# offsets-7x.net
KiCad netlist of a schematic drawn in EAGLE
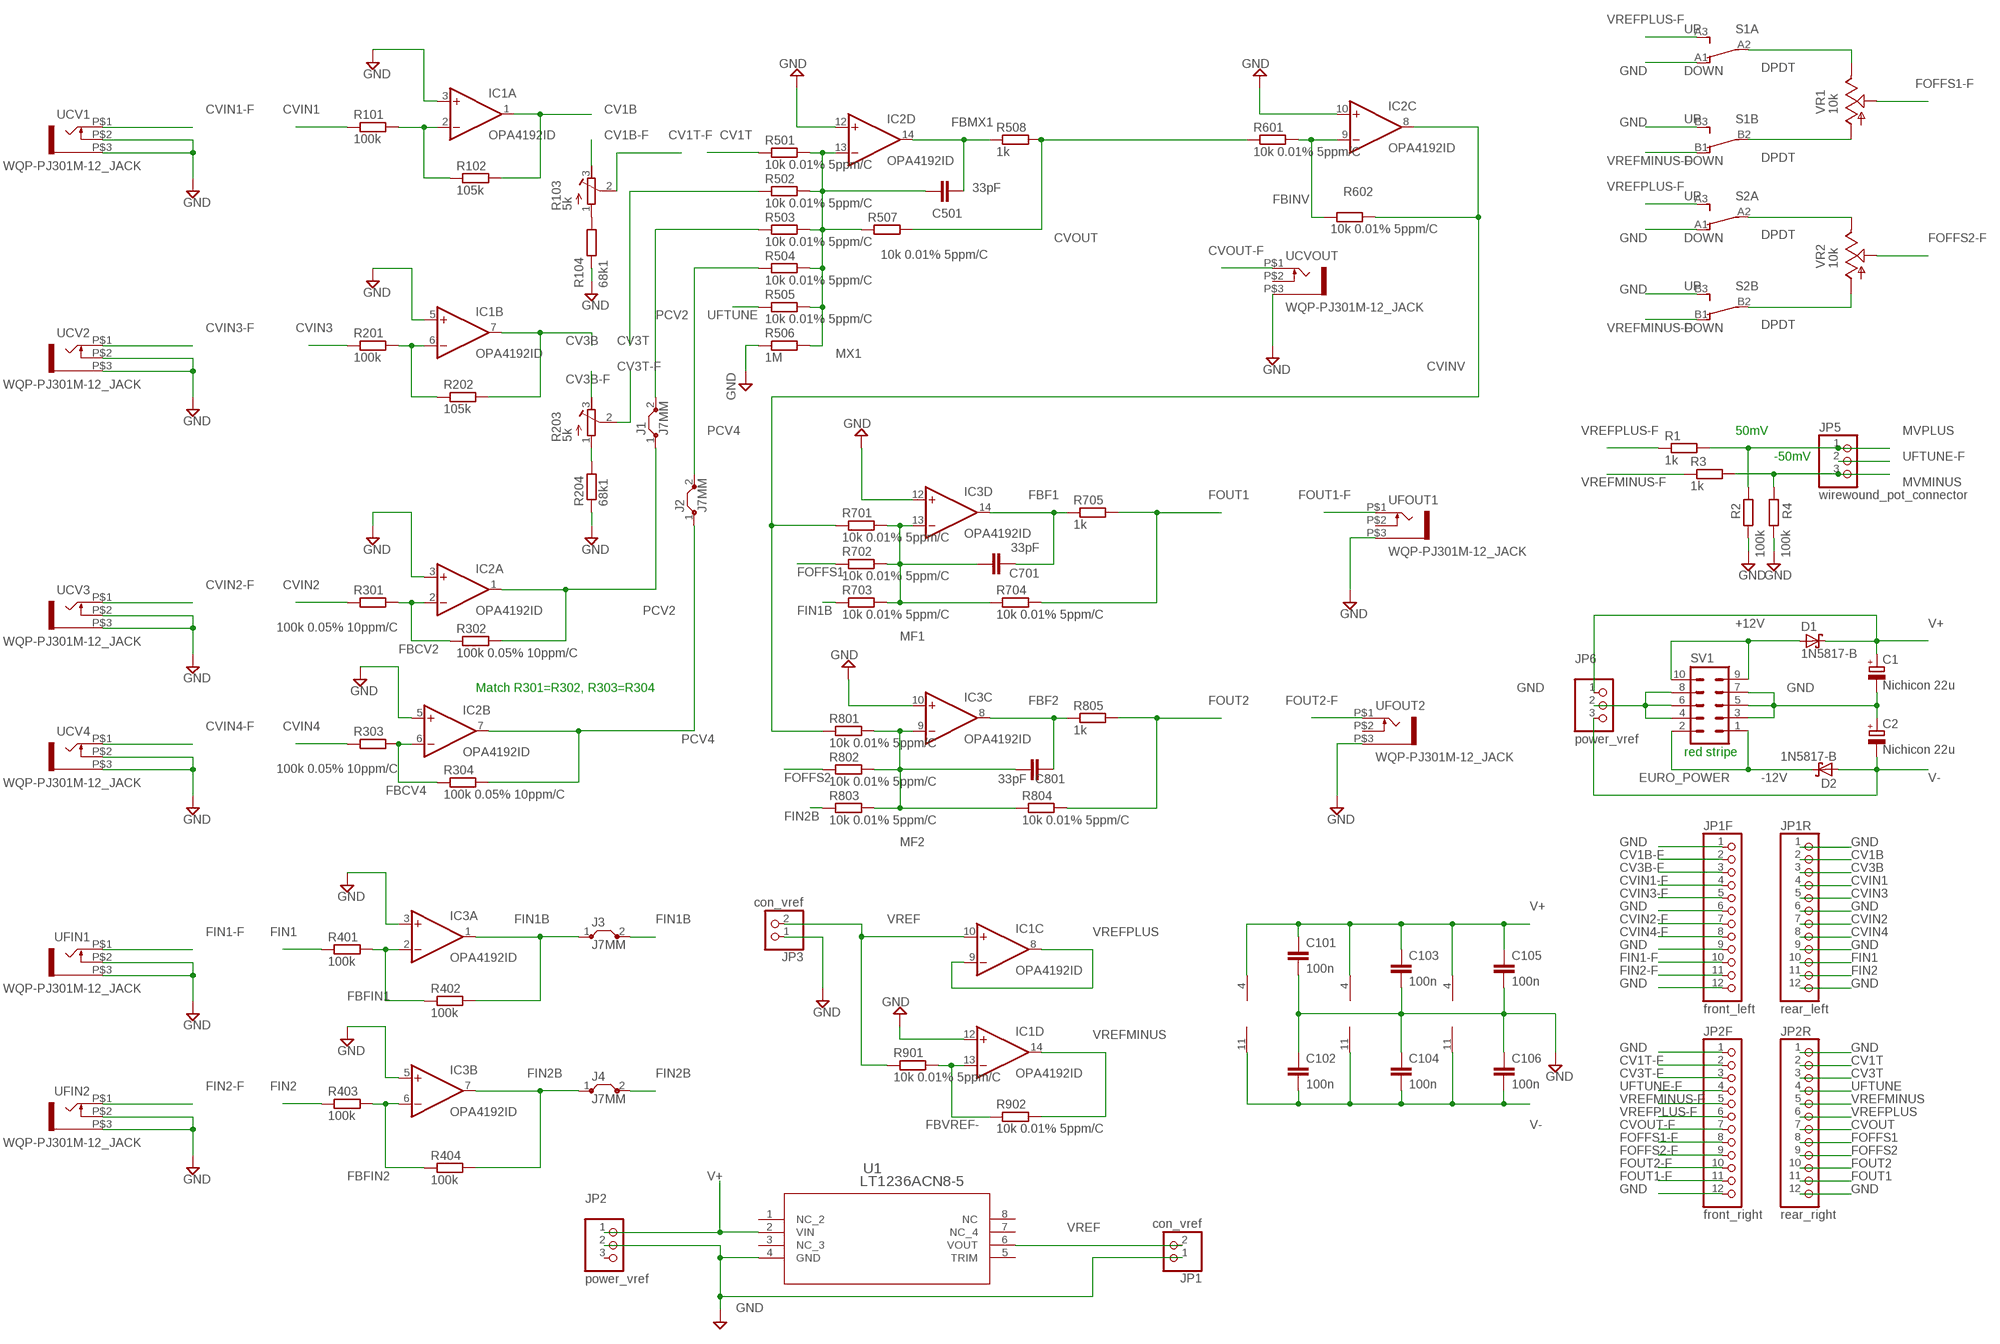
[diagram p0: schematic, sheet 1]

(export (version "E")
  (design (tool "Eeschema 10.0.6"))
  (components
    (comp (ref "C1")
      (value "Nichicon 22u")
      (footprint "eagle-import:E2,5-5")
      (libsource (lib "eagle-import") (part "CPOL-EUE2.5-5"))
    )
    (comp (ref "C2")
      (value "Nichicon 22u")
      (footprint "eagle-import:E2,5-5")
      (libsource (lib "eagle-import") (part "CPOL-EUE2.5-5"))
    )
    (comp (ref "C101")
      (value "100n")
      (footprint "eagle-import:C1206")
      (libsource (lib "eagle-import") (part "C-EUC1206"))
    )
    (comp (ref "C102")
      (value "100n")
      (footprint "eagle-import:C1206")
      (libsource (lib "eagle-import") (part "C-EUC1206"))
    )
    (comp (ref "C103")
      (value "100n")
      (footprint "eagle-import:C1206")
      (libsource (lib "eagle-import") (part "C-EUC1206"))
    )
    (comp (ref "C104")
      (value "100n")
      (footprint "eagle-import:C1206")
      (libsource (lib "eagle-import") (part "C-EUC1206"))
    )
    (comp (ref "C105")
      (value "100n")
      (footprint "eagle-import:C1206")
      (libsource (lib "eagle-import") (part "C-EUC1206"))
    )
    (comp (ref "C106")
      (value "100n")
      (footprint "eagle-import:C1206")
      (libsource (lib "eagle-import") (part "C-EUC1206"))
    )
    (comp (ref "C501")
      (value "33pF")
      (footprint "eagle-import:C0805K")
      (libsource (lib "eagle-import") (part "C-EUC0805K"))
    )
    (comp (ref "C701")
      (value "33pF")
      (footprint "eagle-import:C0805K")
      (libsource (lib "eagle-import") (part "C-EUC0805K"))
    )
    (comp (ref "C801")
      (value "33pF")
      (footprint "eagle-import:C0805K")
      (libsource (lib "eagle-import") (part "C-EUC0805K"))
    )
    (comp (ref "D1")
      (value "1N5817-B")
      (footprint "eagle-import:DO41-7.6")
      (libsource (lib "eagle-import") (part "1N5817-B"))
    )
    (comp (ref "D2")
      (value "1N5817-B")
      (footprint "eagle-import:DO41-7.6")
      (libsource (lib "eagle-import") (part "1N5817-B"))
    )
    (comp (ref "IC1")
      (value "OPA4192ID")
      (footprint "eagle-import:SO14")
      (libsource (lib "eagle-import") (part "TL074D"))
    )
    (comp (ref "IC2")
      (value "OPA4192ID")
      (footprint "eagle-import:SO14")
      (libsource (lib "eagle-import") (part "TL074D"))
    )
    (comp (ref "IC3")
      (value "OPA4192ID")
      (footprint "eagle-import:SO14")
      (libsource (lib "eagle-import") (part "TL074D"))
    )
    (comp (ref "J1")
      (value "J7MM")
      (footprint "eagle-import:07")
      (libsource (lib "eagle-import") (part "J7MM"))
    )
    (comp (ref "J2")
      (value "J7MM")
      (footprint "eagle-import:07")
      (libsource (lib "eagle-import") (part "J7MM"))
    )
    (comp (ref "J3")
      (value "J7MM")
      (footprint "eagle-import:07")
      (libsource (lib "eagle-import") (part "J7MM"))
    )
    (comp (ref "J4")
      (value "J7MM")
      (footprint "eagle-import:07")
      (libsource (lib "eagle-import") (part "J7MM"))
    )
    (comp (ref "JP1")
      (value "con_vref")
      (footprint "eagle-import:1X02")
      (libsource (lib "eagle-import") (part "PINHD-1X2"))
    )
    (comp (ref "JP1F")
      (value "front_left")
      (footprint "eagle-import:1X12")
      (libsource (lib "eagle-import") (part "PINHD-1X12"))
    )
    (comp (ref "JP1R")
      (value "rear_left")
      (footprint "eagle-import:1X12")
      (libsource (lib "eagle-import") (part "PINHD-1X12"))
    )
    (comp (ref "JP2")
      (value "power_vref")
      (footprint "eagle-import:1X03")
      (libsource (lib "eagle-import") (part "PINHD-1X3"))
    )
    (comp (ref "JP2F")
      (value "front_right")
      (footprint "eagle-import:1X12")
      (libsource (lib "eagle-import") (part "PINHD-1X12"))
    )
    (comp (ref "JP2R")
      (value "rear_right")
      (footprint "eagle-import:1X12")
      (libsource (lib "eagle-import") (part "PINHD-1X12"))
    )
    (comp (ref "JP3")
      (value "con_vref")
      (footprint "eagle-import:1X02")
      (libsource (lib "eagle-import") (part "PINHD-1X2"))
    )
    (comp (ref "JP5")
      (value "wirewound_pot_connector")
      (footprint "eagle-import:1X03")
      (libsource (lib "eagle-import") (part "PINHD-1X3"))
    )
    (comp (ref "JP6")
      (value "power_vref")
      (footprint "eagle-import:1X03")
      (libsource (lib "eagle-import") (part "PINHD-1X3"))
    )
    (comp (ref "R1")
      (value "1k")
      (footprint "eagle-import:R0805W")
      (libsource (lib "eagle-import") (part "R-EU_R0805W"))
    )
    (comp (ref "R2")
      (value "100k")
      (footprint "eagle-import:R0805W")
      (libsource (lib "eagle-import") (part "R-EU_R0805W"))
    )
    (comp (ref "R3")
      (value "1k")
      (footprint "eagle-import:R0805W")
      (libsource (lib "eagle-import") (part "R-EU_R0805W"))
    )
    (comp (ref "R4")
      (value "100k")
      (footprint "eagle-import:R0805W")
      (libsource (lib "eagle-import") (part "R-EU_R0805W"))
    )
    (comp (ref "R101")
      (value "100k")
      (footprint "eagle-import:R0805W")
      (libsource (lib "eagle-import") (part "R-EU_R0805W"))
    )
    (comp (ref "R102")
      (value "105k")
      (footprint "eagle-import:R0805W")
      (libsource (lib "eagle-import") (part "R-EU_R0805W"))
    )
    (comp (ref "R103")
      (value "5k")
      (footprint "eagle-import:RTRIM3296W")
      (libsource (lib "eagle-import") (part "R-TRIMM3296W"))
    )
    (comp (ref "R104")
      (value "68k1")
      (footprint "eagle-import:R0805W")
      (libsource (lib "eagle-import") (part "R-EU_R0805W"))
    )
    (comp (ref "R201")
      (value "100k")
      (footprint "eagle-import:R0805W")
      (libsource (lib "eagle-import") (part "R-EU_R0805W"))
    )
    (comp (ref "R202")
      (value "105k")
      (footprint "eagle-import:R0805W")
      (libsource (lib "eagle-import") (part "R-EU_R0805W"))
    )
    (comp (ref "R203")
      (value "5k")
      (footprint "eagle-import:RTRIM3296W")
      (libsource (lib "eagle-import") (part "R-TRIMM3296W"))
    )
    (comp (ref "R204")
      (value "68k1")
      (footprint "eagle-import:R0805W")
      (libsource (lib "eagle-import") (part "R-EU_R0805W"))
    )
    (comp (ref "R301")
      (value "100k 0.05% 10ppm/C")
      (footprint "eagle-import:R0805W")
      (libsource (lib "eagle-import") (part "R-EU_R0805W"))
    )
    (comp (ref "R302")
      (value "100k 0.05% 10ppm/C")
      (footprint "eagle-import:R0805W")
      (libsource (lib "eagle-import") (part "R-EU_R0805W"))
    )
    (comp (ref "R303")
      (value "100k 0.05% 10ppm/C")
      (footprint "eagle-import:R0805W")
      (libsource (lib "eagle-import") (part "R-EU_R0805W"))
    )
    (comp (ref "R304")
      (value "100k 0.05% 10ppm/C")
      (footprint "eagle-import:R0805W")
      (libsource (lib "eagle-import") (part "R-EU_R0805W"))
    )
    (comp (ref "R401")
      (value "100k")
      (footprint "eagle-import:R0805W")
      (libsource (lib "eagle-import") (part "R-EU_R0805W"))
    )
    (comp (ref "R402")
      (value "100k")
      (footprint "eagle-import:R0805W")
      (libsource (lib "eagle-import") (part "R-EU_R0805W"))
    )
    (comp (ref "R403")
      (value "100k")
      (footprint "eagle-import:R0805W")
      (libsource (lib "eagle-import") (part "R-EU_R0805W"))
    )
    (comp (ref "R404")
      (value "100k")
      (footprint "eagle-import:R0805W")
      (libsource (lib "eagle-import") (part "R-EU_R0805W"))
    )
    (comp (ref "R501")
      (value "10k 0.01% 5ppm/C")
      (footprint "eagle-import:R0805W")
      (libsource (lib "eagle-import") (part "R-EU_R0805W"))
    )
    (comp (ref "R502")
      (value "10k 0.01% 5ppm/C")
      (footprint "eagle-import:R0805W")
      (libsource (lib "eagle-import") (part "R-EU_R0805W"))
    )
    (comp (ref "R503")
      (value "10k 0.01% 5ppm/C")
      (footprint "eagle-import:R0805W")
      (libsource (lib "eagle-import") (part "R-EU_R0805W"))
    )
    (comp (ref "R504")
      (value "10k 0.01% 5ppm/C")
      (footprint "eagle-import:R0805W")
      (libsource (lib "eagle-import") (part "R-EU_R0805W"))
    )
    (comp (ref "R505")
      (value "10k 0.01% 5ppm/C")
      (footprint "eagle-import:R0805W")
      (libsource (lib "eagle-import") (part "R-EU_R0805W"))
    )
    (comp (ref "R506")
      (value "1M")
      (footprint "eagle-import:R0805W")
      (libsource (lib "eagle-import") (part "R-EU_R0805W"))
    )
    (comp (ref "R507")
      (value "10k 0.01% 5ppm/C")
      (footprint "eagle-import:R0805W")
      (libsource (lib "eagle-import") (part "R-EU_R0805W"))
    )
    (comp (ref "R508")
      (value "1k")
      (footprint "eagle-import:R0805W")
      (libsource (lib "eagle-import") (part "R-EU_R0805W"))
    )
    (comp (ref "R601")
      (value "10k 0.01% 5ppm/C")
      (footprint "eagle-import:R0805W")
      (libsource (lib "eagle-import") (part "R-EU_R0805W"))
    )
    (comp (ref "R602")
      (value "10k 0.01% 5ppm/C")
      (footprint "eagle-import:R0805W")
      (libsource (lib "eagle-import") (part "R-EU_R0805W"))
    )
    (comp (ref "R701")
      (value "10k 0.01% 5ppm/C")
      (footprint "eagle-import:R0805W")
      (libsource (lib "eagle-import") (part "R-EU_R0805W"))
    )
    (comp (ref "R702")
      (value "10k 0.01% 5ppm/C")
      (footprint "eagle-import:R0805W")
      (libsource (lib "eagle-import") (part "R-EU_R0805W"))
    )
    (comp (ref "R703")
      (value "10k 0.01% 5ppm/C")
      (footprint "eagle-import:R0805W")
      (libsource (lib "eagle-import") (part "R-EU_R0805W"))
    )
    (comp (ref "R704")
      (value "10k 0.01% 5ppm/C")
      (footprint "eagle-import:R0805W")
      (libsource (lib "eagle-import") (part "R-EU_R0805W"))
    )
    (comp (ref "R705")
      (value "1k")
      (footprint "eagle-import:R0805W")
      (libsource (lib "eagle-import") (part "R-EU_R0805W"))
    )
    (comp (ref "R801")
      (value "10k 0.01% 5ppm/C")
      (footprint "eagle-import:R0805W")
      (libsource (lib "eagle-import") (part "R-EU_R0805W"))
    )
    (comp (ref "R802")
      (value "10k 0.01% 5ppm/C")
      (footprint "eagle-import:R0805W")
      (libsource (lib "eagle-import") (part "R-EU_R0805W"))
    )
    (comp (ref "R803")
      (value "10k 0.01% 5ppm/C")
      (footprint "eagle-import:R0805W")
      (libsource (lib "eagle-import") (part "R-EU_R0805W"))
    )
    (comp (ref "R804")
      (value "10k 0.01% 5ppm/C")
      (footprint "eagle-import:R0805W")
      (libsource (lib "eagle-import") (part "R-EU_R0805W"))
    )
    (comp (ref "R805")
      (value "1k")
      (footprint "eagle-import:R0805W")
      (libsource (lib "eagle-import") (part "R-EU_R0805W"))
    )
    (comp (ref "R901")
      (value "10k 0.01% 5ppm/C")
      (footprint "eagle-import:R0805W")
      (libsource (lib "eagle-import") (part "R-EU_R0805W"))
    )
    (comp (ref "R902")
      (value "10k 0.01% 5ppm/C")
      (footprint "eagle-import:R0805W")
      (libsource (lib "eagle-import") (part "R-EU_R0805W"))
    )
    (comp (ref "S1")
      (value "DPDT")
      (footprint "eagle-import:DPDT-VERTICAL-TOP-SUBMINI-MULTICOMP")
      (libsource (lib "eagle-import") (part "DPDT-VERTICAL-DOWNTOP-SUBMINI"))
    )
    (comp (ref "S2")
      (value "DPDT")
      (footprint "eagle-import:DPDT-VERTICAL-TOP-SUBMINI-MULTICOMP")
      (libsource (lib "eagle-import") (part "DPDT-VERTICAL-DOWNTOP-SUBMINI"))
    )
    (comp (ref "SV1")
      (value "EURO_POWER")
      (footprint "eagle-import:EURO_POWER_HEADER")
      (libsource (lib "eagle-import") (part "EURO_POWER_HEADERREGULAR"))
    )
    (comp (ref "U1")
      (value "LT1236ACN8-5")
      (footprint "eagle-import:PDIP-8_N")
      (fields (field (name "MANUFACTURER_PART_NUMBER") "lt1236acn810"))
      (libsource (lib "eagle-import") (part "LT1236ACN8-10"))
    )
    (comp (ref "UCV1")
      (value "WQP-PJ301M-12_JACK")
      (footprint "eagle-import:WQP-PJ301M-12_JACK")
      (libsource (lib "eagle-import") (part "WQP-PJ301M-12_JACK"))
    )
    (comp (ref "UCV2")
      (value "WQP-PJ301M-12_JACK")
      (footprint "eagle-import:WQP-PJ301M-12_JACK")
      (libsource (lib "eagle-import") (part "WQP-PJ301M-12_JACK"))
    )
    (comp (ref "UCV3")
      (value "WQP-PJ301M-12_JACK")
      (footprint "eagle-import:WQP-PJ301M-12_JACK")
      (libsource (lib "eagle-import") (part "WQP-PJ301M-12_JACK"))
    )
    (comp (ref "UCV4")
      (value "WQP-PJ301M-12_JACK")
      (footprint "eagle-import:WQP-PJ301M-12_JACK")
      (libsource (lib "eagle-import") (part "WQP-PJ301M-12_JACK"))
    )
    (comp (ref "UCVOUT")
      (value "WQP-PJ301M-12_JACK")
      (footprint "eagle-import:WQP-PJ301M-12_JACK")
      (libsource (lib "eagle-import") (part "WQP-PJ301M-12_JACK"))
    )
    (comp (ref "UFIN1")
      (value "WQP-PJ301M-12_JACK")
      (footprint "eagle-import:WQP-PJ301M-12_JACK")
      (libsource (lib "eagle-import") (part "WQP-PJ301M-12_JACK"))
    )
    (comp (ref "UFIN2")
      (value "WQP-PJ301M-12_JACK")
      (footprint "eagle-import:WQP-PJ301M-12_JACK")
      (libsource (lib "eagle-import") (part "WQP-PJ301M-12_JACK"))
    )
    (comp (ref "UFOUT1")
      (value "WQP-PJ301M-12_JACK")
      (footprint "eagle-import:WQP-PJ301M-12_JACK")
      (libsource (lib "eagle-import") (part "WQP-PJ301M-12_JACK"))
    )
    (comp (ref "UFOUT2")
      (value "WQP-PJ301M-12_JACK")
      (footprint "eagle-import:WQP-PJ301M-12_JACK")
      (libsource (lib "eagle-import") (part "WQP-PJ301M-12_JACK"))
    )
    (comp (ref "VR1")
      (value "10k")
      (footprint "eagle-import:9MM_SNAP-IN_POT")
      (libsource (lib "eagle-import") (part "9MM_SNAP-IN_POT_"))
    )
    (comp (ref "VR2")
      (value "10k")
      (footprint "eagle-import:9MM_SNAP-IN_POT")
      (libsource (lib "eagle-import") (part "9MM_SNAP-IN_POT_"))
    )
  )
  (nets
    (net (code "1") (name "/+12V") (class "Default")
      (node (ref "D1") (pin "A") (pinfunction "A_A") (pintype "passive"))
      (node (ref "SV1") (pin "10") (pinfunction "10_10") (pintype "passive"))
      (node (ref "SV1") (pin "9") (pinfunction "9_9") (pintype "passive"))
    )
    (net (code "2") (name "/-12V") (class "Default")
      (node (ref "D2") (pin "C") (pinfunction "C_C") (pintype "passive"))
      (node (ref "SV1") (pin "1") (pinfunction "1_1") (pintype "passive"))
      (node (ref "SV1") (pin "2") (pinfunction "2_2") (pintype "passive"))
    )
    (net (code "3") (name "/CV1B") (class "Default")
      (node (ref "IC1") (pin "1") (pinfunction "OUT_1") (pintype "output"))
      (node (ref "JP1R") (pin "2") (pinfunction "2_2") (pintype "passive"))
      (node (ref "R102") (pin "2") (pinfunction "2_2") (pintype "passive"))
    )
    (net (code "4") (name "/CV1B-F") (class "Default")
      (node (ref "JP1F") (pin "2") (pinfunction "2_2") (pintype "passive"))
      (node (ref "R103") (pin "3") (pinfunction "E_3") (pintype "passive"))
    )
    (net (code "5") (name "/CV1T") (class "Default")
      (node (ref "JP2R") (pin "2") (pinfunction "2_2") (pintype "passive"))
      (node (ref "R501") (pin "1") (pinfunction "1_1") (pintype "passive"))
    )
    (net (code "6") (name "/CV1T-F") (class "Default")
      (node (ref "JP2F") (pin "2") (pinfunction "2_2") (pintype "passive"))
      (node (ref "R103") (pin "2") (pinfunction "S_2") (pintype "passive"))
    )
    (net (code "7") (name "/CV3B") (class "Default")
      (node (ref "IC1") (pin "7") (pinfunction "OUT_7") (pintype "output"))
      (node (ref "JP1R") (pin "3") (pinfunction "3_3") (pintype "passive"))
      (node (ref "R202") (pin "2") (pinfunction "2_2") (pintype "passive"))
    )
    (net (code "8") (name "/CV3B-F") (class "Default")
      (node (ref "JP1F") (pin "3") (pinfunction "3_3") (pintype "passive"))
      (node (ref "R203") (pin "3") (pinfunction "E_3") (pintype "passive"))
    )
    (net (code "9") (name "/CV3T") (class "Default")
      (node (ref "JP2R") (pin "3") (pinfunction "3_3") (pintype "passive"))
      (node (ref "R502") (pin "1") (pinfunction "1_1") (pintype "passive"))
    )
    (net (code "10") (name "/CV3T-F") (class "Default")
      (node (ref "JP2F") (pin "3") (pinfunction "3_3") (pintype "passive"))
      (node (ref "R203") (pin "2") (pinfunction "S_2") (pintype "passive"))
    )
    (net (code "11") (name "/CVIN1") (class "Default")
      (node (ref "JP1R") (pin "4") (pinfunction "4_4") (pintype "passive"))
      (node (ref "R101") (pin "1") (pinfunction "1_1") (pintype "passive"))
    )
    (net (code "12") (name "/CVIN1-F") (class "Default")
      (node (ref "JP1F") (pin "4") (pinfunction "4_4") (pintype "passive"))
      (node (ref "UCV1") (pin "P$1") (pinfunction "2_P$1") (pintype "passive"))
    )
    (net (code "13") (name "/CVIN2") (class "Default")
      (node (ref "JP1R") (pin "7") (pinfunction "7_7") (pintype "passive"))
      (node (ref "R301") (pin "1") (pinfunction "1_1") (pintype "passive"))
    )
    (net (code "14") (name "/CVIN2-F") (class "Default")
      (node (ref "JP1F") (pin "7") (pinfunction "7_7") (pintype "passive"))
      (node (ref "UCV3") (pin "P$1") (pinfunction "2_P$1") (pintype "passive"))
    )
    (net (code "15") (name "/CVIN3") (class "Default")
      (node (ref "JP1R") (pin "5") (pinfunction "5_5") (pintype "passive"))
      (node (ref "R201") (pin "1") (pinfunction "1_1") (pintype "passive"))
    )
    (net (code "16") (name "/CVIN3-F") (class "Default")
      (node (ref "JP1F") (pin "5") (pinfunction "5_5") (pintype "passive"))
      (node (ref "UCV2") (pin "P$1") (pinfunction "2_P$1") (pintype "passive"))
    )
    (net (code "17") (name "/CVIN4") (class "Default")
      (node (ref "JP1R") (pin "8") (pinfunction "8_8") (pintype "passive"))
      (node (ref "R303") (pin "1") (pinfunction "1_1") (pintype "passive"))
    )
    (net (code "18") (name "/CVIN4-F") (class "Default")
      (node (ref "JP1F") (pin "8") (pinfunction "8_8") (pintype "passive"))
      (node (ref "UCV4") (pin "P$1") (pinfunction "2_P$1") (pintype "passive"))
    )
    (net (code "19") (name "/CVINV") (class "Default")
      (node (ref "IC2") (pin "8") (pinfunction "OUT_8") (pintype "output"))
      (node (ref "R602") (pin "2") (pinfunction "2_2") (pintype "passive"))
      (node (ref "R701") (pin "1") (pinfunction "1_1") (pintype "passive"))
      (node (ref "R801") (pin "1") (pinfunction "1_1") (pintype "passive"))
    )
    (net (code "20") (name "/CVOUT") (class "Default")
      (node (ref "JP2R") (pin "7") (pinfunction "7_7") (pintype "passive"))
      (node (ref "R507") (pin "2") (pinfunction "2_2") (pintype "passive"))
      (node (ref "R508") (pin "2") (pinfunction "2_2") (pintype "passive"))
      (node (ref "R601") (pin "1") (pinfunction "1_1") (pintype "passive"))
    )
    (net (code "21") (name "/CVOUT-F") (class "Default")
      (node (ref "JP2F") (pin "7") (pinfunction "7_7") (pintype "passive"))
      (node (ref "UCVOUT") (pin "P$1") (pinfunction "2_P$1") (pintype "passive"))
    )
    (net (code "22") (name "/FBCV2") (class "Default")
      (node (ref "IC2") (pin "2") (pinfunction "-IN_2") (pintype "input"))
      (node (ref "R301") (pin "2") (pinfunction "2_2") (pintype "passive"))
      (node (ref "R302") (pin "1") (pinfunction "1_1") (pintype "passive"))
    )
    (net (code "23") (name "/FBCV4") (class "Default")
      (node (ref "IC2") (pin "6") (pinfunction "-IN_6") (pintype "input"))
      (node (ref "R303") (pin "2") (pinfunction "2_2") (pintype "passive"))
      (node (ref "R304") (pin "1") (pinfunction "1_1") (pintype "passive"))
    )
    (net (code "24") (name "/FBF1") (class "Default")
      (node (ref "C701") (pin "2") (pinfunction "2_2") (pintype "passive"))
      (node (ref "IC3") (pin "14") (pinfunction "OUT_14") (pintype "output"))
      (node (ref "R705") (pin "1") (pinfunction "1_1") (pintype "passive"))
    )
    (net (code "25") (name "/FBF2") (class "Default")
      (node (ref "C801") (pin "2") (pinfunction "2_2") (pintype "passive"))
      (node (ref "IC3") (pin "8") (pinfunction "OUT_8") (pintype "output"))
      (node (ref "R805") (pin "1") (pinfunction "1_1") (pintype "passive"))
    )
    (net (code "26") (name "/FBFIN1") (class "Default")
      (node (ref "IC3") (pin "2") (pinfunction "-IN_2") (pintype "input"))
      (node (ref "R401") (pin "2") (pinfunction "2_2") (pintype "passive"))
      (node (ref "R402") (pin "1") (pinfunction "1_1") (pintype "passive"))
    )
    (net (code "27") (name "/FBFIN2") (class "Default")
      (node (ref "IC3") (pin "6") (pinfunction "-IN_6") (pintype "input"))
      (node (ref "R403") (pin "2") (pinfunction "2_2") (pintype "passive"))
      (node (ref "R404") (pin "1") (pinfunction "1_1") (pintype "passive"))
    )
    (net (code "28") (name "/FBINV") (class "Default")
      (node (ref "IC2") (pin "9") (pinfunction "-IN_9") (pintype "input"))
      (node (ref "R601") (pin "2") (pinfunction "2_2") (pintype "passive"))
      (node (ref "R602") (pin "1") (pinfunction "1_1") (pintype "passive"))
    )
    (net (code "29") (name "/FBMX1") (class "Default")
      (node (ref "C501") (pin "2") (pinfunction "2_2") (pintype "passive"))
      (node (ref "IC2") (pin "14") (pinfunction "OUT_14") (pintype "output"))
      (node (ref "R508") (pin "1") (pinfunction "1_1") (pintype "passive"))
    )
    (net (code "30") (name "/FBVREF-") (class "Default")
      (node (ref "IC1") (pin "13") (pinfunction "-IN_13") (pintype "input"))
      (node (ref "R901") (pin "2") (pinfunction "2_2") (pintype "passive"))
      (node (ref "R902") (pin "1") (pinfunction "1_1") (pintype "passive"))
    )
    (net (code "31") (name "/FIN1") (class "Default")
      (node (ref "JP1R") (pin "10") (pinfunction "10_10") (pintype "passive"))
      (node (ref "R401") (pin "1") (pinfunction "1_1") (pintype "passive"))
    )
    (net (code "32") (name "/FIN1-F") (class "Default")
      (node (ref "JP1F") (pin "10") (pinfunction "10_10") (pintype "passive"))
      (node (ref "UFIN1") (pin "P$1") (pinfunction "2_P$1") (pintype "passive"))
    )
    (net (code "33") (name "/FIN1B") (class "Default")
      (node (ref "IC3") (pin "1") (pinfunction "OUT_1") (pintype "output"))
      (node (ref "J3") (pin "1") (pinfunction "1_1") (pintype "passive"))
      (node (ref "J3") (pin "2") (pinfunction "2_2") (pintype "passive"))
      (node (ref "R402") (pin "2") (pinfunction "2_2") (pintype "passive"))
      (node (ref "R703") (pin "1") (pinfunction "1_1") (pintype "passive"))
    )
    (net (code "34") (name "/FIN2") (class "Default")
      (node (ref "JP1R") (pin "11") (pinfunction "11_11") (pintype "passive"))
      (node (ref "R403") (pin "1") (pinfunction "1_1") (pintype "passive"))
    )
    (net (code "35") (name "/FIN2-F") (class "Default")
      (node (ref "JP1F") (pin "11") (pinfunction "11_11") (pintype "passive"))
      (node (ref "UFIN2") (pin "P$1") (pinfunction "2_P$1") (pintype "passive"))
    )
    (net (code "36") (name "/FIN2B") (class "Default")
      (node (ref "IC3") (pin "7") (pinfunction "OUT_7") (pintype "output"))
      (node (ref "J4") (pin "1") (pinfunction "1_1") (pintype "passive"))
      (node (ref "J4") (pin "2") (pinfunction "2_2") (pintype "passive"))
      (node (ref "R404") (pin "2") (pinfunction "2_2") (pintype "passive"))
      (node (ref "R803") (pin "1") (pinfunction "1_1") (pintype "passive"))
    )
    (net (code "37") (name "/FOFFS1") (class "Default")
      (node (ref "JP2R") (pin "8") (pinfunction "8_8") (pintype "passive"))
      (node (ref "R702") (pin "1") (pinfunction "1_1") (pintype "passive"))
    )
    (net (code "38") (name "/FOFFS1-F") (class "Default")
      (node (ref "JP2F") (pin "8") (pinfunction "8_8") (pintype "passive"))
      (node (ref "VR1") (pin "2") (pinfunction "S_2") (pintype "passive"))
    )
    (net (code "39") (name "/FOFFS2") (class "Default")
      (node (ref "JP2R") (pin "9") (pinfunction "9_9") (pintype "passive"))
      (node (ref "R802") (pin "1") (pinfunction "1_1") (pintype "passive"))
    )
    (net (code "40") (name "/FOFFS2-F") (class "Default")
      (node (ref "JP2F") (pin "9") (pinfunction "9_9") (pintype "passive"))
      (node (ref "VR2") (pin "2") (pinfunction "S_2") (pintype "passive"))
    )
    (net (code "41") (name "/FOUT1") (class "Default")
      (node (ref "JP2R") (pin "11") (pinfunction "11_11") (pintype "passive"))
      (node (ref "R704") (pin "2") (pinfunction "2_2") (pintype "passive"))
      (node (ref "R705") (pin "2") (pinfunction "2_2") (pintype "passive"))
    )
    (net (code "42") (name "/FOUT1-F") (class "Default")
      (node (ref "JP2F") (pin "11") (pinfunction "11_11") (pintype "passive"))
      (node (ref "UFOUT1") (pin "P$1") (pinfunction "2_P$1") (pintype "passive"))
    )
    (net (code "43") (name "/FOUT2") (class "Default")
      (node (ref "JP2R") (pin "10") (pinfunction "10_10") (pintype "passive"))
      (node (ref "R804") (pin "2") (pinfunction "2_2") (pintype "passive"))
      (node (ref "R805") (pin "2") (pinfunction "2_2") (pintype "passive"))
    )
    (net (code "44") (name "/FOUT2-F") (class "Default")
      (node (ref "JP2F") (pin "10") (pinfunction "10_10") (pintype "passive"))
      (node (ref "UFOUT2") (pin "P$1") (pinfunction "2_P$1") (pintype "passive"))
    )
    (net (code "45") (name "/MF1") (class "Default")
      (node (ref "C701") (pin "1") (pinfunction "1_1") (pintype "passive"))
      (node (ref "IC3") (pin "13") (pinfunction "-IN_13") (pintype "input"))
      (node (ref "R701") (pin "2") (pinfunction "2_2") (pintype "passive"))
      (node (ref "R702") (pin "2") (pinfunction "2_2") (pintype "passive"))
      (node (ref "R703") (pin "2") (pinfunction "2_2") (pintype "passive"))
      (node (ref "R704") (pin "1") (pinfunction "1_1") (pintype "passive"))
    )
    (net (code "46") (name "/MF2") (class "Default")
      (node (ref "C801") (pin "1") (pinfunction "1_1") (pintype "passive"))
      (node (ref "IC3") (pin "9") (pinfunction "-IN_9") (pintype "input"))
      (node (ref "R801") (pin "2") (pinfunction "2_2") (pintype "passive"))
      (node (ref "R802") (pin "2") (pinfunction "2_2") (pintype "passive"))
      (node (ref "R803") (pin "2") (pinfunction "2_2") (pintype "passive"))
      (node (ref "R804") (pin "1") (pinfunction "1_1") (pintype "passive"))
    )
    (net (code "47") (name "/MVMINUS") (class "Default")
      (node (ref "JP5") (pin "3") (pinfunction "3_3") (pintype "passive"))
      (node (ref "R3") (pin "2") (pinfunction "2_2") (pintype "passive"))
      (node (ref "R4") (pin "2") (pinfunction "2_2") (pintype "passive"))
    )
    (net (code "48") (name "/MVPLUS") (class "Default")
      (node (ref "JP5") (pin "1") (pinfunction "1_1") (pintype "passive"))
      (node (ref "R1") (pin "2") (pinfunction "2_2") (pintype "passive"))
      (node (ref "R2") (pin "2") (pinfunction "2_2") (pintype "passive"))
    )
    (net (code "49") (name "/MX1") (class "Default")
      (node (ref "C501") (pin "1") (pinfunction "1_1") (pintype "passive"))
      (node (ref "IC2") (pin "13") (pinfunction "-IN_13") (pintype "input"))
      (node (ref "R501") (pin "2") (pinfunction "2_2") (pintype "passive"))
      (node (ref "R502") (pin "2") (pinfunction "2_2") (pintype "passive"))
      (node (ref "R503") (pin "2") (pinfunction "2_2") (pintype "passive"))
      (node (ref "R504") (pin "2") (pinfunction "2_2") (pintype "passive"))
      (node (ref "R505") (pin "2") (pinfunction "2_2") (pintype "passive"))
      (node (ref "R506") (pin "2") (pinfunction "2_2") (pintype "passive"))
      (node (ref "R507") (pin "1") (pinfunction "1_1") (pintype "passive"))
    )
    (net (code "50") (name "/PCV2") (class "Default")
      (node (ref "IC2") (pin "1") (pinfunction "OUT_1") (pintype "output"))
      (node (ref "J1") (pin "1") (pinfunction "1_1") (pintype "passive"))
      (node (ref "J1") (pin "2") (pinfunction "2_2") (pintype "passive"))
      (node (ref "R302") (pin "2") (pinfunction "2_2") (pintype "passive"))
      (node (ref "R503") (pin "1") (pinfunction "1_1") (pintype "passive"))
    )
    (net (code "51") (name "/PCV4") (class "Default")
      (node (ref "IC2") (pin "7") (pinfunction "OUT_7") (pintype "output"))
      (node (ref "J2") (pin "1") (pinfunction "1_1") (pintype "passive"))
      (node (ref "J2") (pin "2") (pinfunction "2_2") (pintype "passive"))
      (node (ref "R304") (pin "2") (pinfunction "2_2") (pintype "passive"))
      (node (ref "R504") (pin "1") (pinfunction "1_1") (pintype "passive"))
    )
    (net (code "52") (name "/UFTUNE") (class "Default")
      (node (ref "JP2R") (pin "4") (pinfunction "4_4") (pintype "passive"))
      (node (ref "R505") (pin "1") (pinfunction "1_1") (pintype "passive"))
    )
    (net (code "53") (name "/UFTUNE-F") (class "Default")
      (node (ref "JP2F") (pin "4") (pinfunction "4_4") (pintype "passive"))
      (node (ref "JP5") (pin "2") (pinfunction "2_2") (pintype "passive"))
    )
    (net (code "54") (name "/V+") (class "Default")
      (node (ref "C1") (pin "+") (pinfunction "+_+") (pintype "passive"))
      (node (ref "C101") (pin "1") (pinfunction "1_1") (pintype "passive"))
      (node (ref "C103") (pin "1") (pinfunction "1_1") (pintype "passive"))
      (node (ref "C105") (pin "1") (pinfunction "1_1") (pintype "passive"))
      (node (ref "D1") (pin "C") (pinfunction "C_C") (pintype "passive"))
      (node (ref "IC1") (pin "4") (pinfunction "V+_4") (pintype "power_in"))
      (node (ref "IC2") (pin "4") (pinfunction "V+_4") (pintype "power_in"))
      (node (ref "IC3") (pin "4") (pinfunction "V+_4") (pintype "power_in"))
      (node (ref "JP2") (pin "1") (pinfunction "1_1") (pintype "passive"))
      (node (ref "JP6") (pin "1") (pinfunction "1_1") (pintype "passive"))
      (node (ref "U1") (pin "2") (pinfunction "VIN_2") (pintype "input"))
    )
    (net (code "55") (name "/V-") (class "Default")
      (node (ref "C102") (pin "2") (pinfunction "2_2") (pintype "passive"))
      (node (ref "C104") (pin "2") (pinfunction "2_2") (pintype "passive"))
      (node (ref "C106") (pin "2") (pinfunction "2_2") (pintype "passive"))
      (node (ref "C2") (pin "-") (pinfunction "-_-") (pintype "passive"))
      (node (ref "D2") (pin "A") (pinfunction "A_A") (pintype "passive"))
      (node (ref "IC1") (pin "11") (pinfunction "V-_11") (pintype "power_in"))
      (node (ref "IC2") (pin "11") (pinfunction "V-_11") (pintype "power_in"))
      (node (ref "IC3") (pin "11") (pinfunction "V-_11") (pintype "power_in"))
      (node (ref "JP6") (pin "3") (pinfunction "3_3") (pintype "passive"))
    )
    (net (code "56") (name "/VREF") (class "Default")
      (node (ref "IC1") (pin "10") (pinfunction "+IN_10") (pintype "input"))
      (node (ref "JP1") (pin "2") (pinfunction "2_2") (pintype "passive"))
      (node (ref "JP3") (pin "2") (pinfunction "2_2") (pintype "passive"))
      (node (ref "R901") (pin "1") (pinfunction "1_1") (pintype "passive"))
      (node (ref "U1") (pin "6") (pinfunction "VOUT_6") (pintype "output"))
    )
    (net (code "57") (name "/VREFMINUS") (class "Default")
      (node (ref "IC1") (pin "14") (pinfunction "OUT_14") (pintype "output"))
      (node (ref "JP2R") (pin "5") (pinfunction "5_5") (pintype "passive"))
      (node (ref "R902") (pin "2") (pinfunction "2_2") (pintype "passive"))
    )
    (net (code "58") (name "/VREFMINUS-F") (class "Default")
      (node (ref "JP2F") (pin "5") (pinfunction "5_5") (pintype "passive"))
      (node (ref "R3") (pin "1") (pinfunction "1_1") (pintype "passive"))
      (node (ref "S1") (pin "B1") (pinfunction "1_B1") (pintype "passive"))
      (node (ref "S2") (pin "B1") (pinfunction "1_B1") (pintype "passive"))
    )
    (net (code "59") (name "/VREFPLUS") (class "Default")
      (node (ref "IC1") (pin "8") (pinfunction "OUT_8") (pintype "output"))
      (node (ref "IC1") (pin "9") (pinfunction "-IN_9") (pintype "input"))
      (node (ref "JP2R") (pin "6") (pinfunction "6_6") (pintype "passive"))
    )
    (net (code "60") (name "/VREFPLUS-F") (class "Default")
      (node (ref "JP2F") (pin "6") (pinfunction "6_6") (pintype "passive"))
      (node (ref "R1") (pin "1") (pinfunction "1_1") (pintype "passive"))
      (node (ref "S1") (pin "A3") (pinfunction "3_A3") (pintype "passive"))
      (node (ref "S2") (pin "A3") (pinfunction "3_A3") (pintype "passive"))
    )
    (net (code "61") (name "GND") (class "Default")
      (node (ref "C1") (pin "-") (pinfunction "-_-") (pintype "passive"))
      (node (ref "C101") (pin "2") (pinfunction "2_2") (pintype "passive"))
      (node (ref "C102") (pin "1") (pinfunction "1_1") (pintype "passive"))
      (node (ref "C103") (pin "2") (pinfunction "2_2") (pintype "passive"))
      (node (ref "C104") (pin "1") (pinfunction "1_1") (pintype "passive"))
      (node (ref "C105") (pin "2") (pinfunction "2_2") (pintype "passive"))
      (node (ref "C106") (pin "1") (pinfunction "1_1") (pintype "passive"))
      (node (ref "C2") (pin "+") (pinfunction "+_+") (pintype "passive"))
      (node (ref "IC1") (pin "12") (pinfunction "+IN_12") (pintype "input"))
      (node (ref "IC1") (pin "3") (pinfunction "+IN_3") (pintype "input"))
      (node (ref "IC1") (pin "5") (pinfunction "+IN_5") (pintype "input"))
      (node (ref "IC2") (pin "10") (pinfunction "+IN_10") (pintype "input"))
      (node (ref "IC2") (pin "12") (pinfunction "+IN_12") (pintype "input"))
      (node (ref "IC2") (pin "3") (pinfunction "+IN_3") (pintype "input"))
      (node (ref "IC2") (pin "5") (pinfunction "+IN_5") (pintype "input"))
      (node (ref "IC3") (pin "10") (pinfunction "+IN_10") (pintype "input"))
      (node (ref "IC3") (pin "12") (pinfunction "+IN_12") (pintype "input"))
      (node (ref "IC3") (pin "3") (pinfunction "+IN_3") (pintype "input"))
      (node (ref "IC3") (pin "5") (pinfunction "+IN_5") (pintype "input"))
      (node (ref "JP1") (pin "1") (pinfunction "1_1") (pintype "passive"))
      (node (ref "JP1F") (pin "1") (pinfunction "1_1") (pintype "passive"))
      (node (ref "JP1F") (pin "12") (pinfunction "12_12") (pintype "passive"))
      (node (ref "JP1F") (pin "6") (pinfunction "6_6") (pintype "passive"))
      (node (ref "JP1F") (pin "9") (pinfunction "9_9") (pintype "passive"))
      (node (ref "JP1R") (pin "1") (pinfunction "1_1") (pintype "passive"))
      (node (ref "JP1R") (pin "12") (pinfunction "12_12") (pintype "passive"))
      (node (ref "JP1R") (pin "6") (pinfunction "6_6") (pintype "passive"))
      (node (ref "JP1R") (pin "9") (pinfunction "9_9") (pintype "passive"))
      (node (ref "JP2") (pin "2") (pinfunction "2_2") (pintype "passive"))
      (node (ref "JP2F") (pin "1") (pinfunction "1_1") (pintype "passive"))
      (node (ref "JP2F") (pin "12") (pinfunction "12_12") (pintype "passive"))
      (node (ref "JP2R") (pin "1") (pinfunction "1_1") (pintype "passive"))
      (node (ref "JP2R") (pin "12") (pinfunction "12_12") (pintype "passive"))
      (node (ref "JP3") (pin "1") (pinfunction "1_1") (pintype "passive"))
      (node (ref "JP6") (pin "2") (pinfunction "2_2") (pintype "passive"))
      (node (ref "R104") (pin "1") (pinfunction "1_1") (pintype "passive"))
      (node (ref "R2") (pin "1") (pinfunction "1_1") (pintype "passive"))
      (node (ref "R204") (pin "1") (pinfunction "1_1") (pintype "passive"))
      (node (ref "R4") (pin "1") (pinfunction "1_1") (pintype "passive"))
      (node (ref "R506") (pin "1") (pinfunction "1_1") (pintype "passive"))
      (node (ref "S1") (pin "A1") (pinfunction "1_A1") (pintype "passive"))
      (node (ref "S1") (pin "B3") (pinfunction "3_B3") (pintype "passive"))
      (node (ref "S2") (pin "A1") (pinfunction "1_A1") (pintype "passive"))
      (node (ref "S2") (pin "B3") (pinfunction "3_B3") (pintype "passive"))
      (node (ref "SV1") (pin "3") (pinfunction "3_3") (pintype "passive"))
      (node (ref "SV1") (pin "4") (pinfunction "4_4") (pintype "passive"))
      (node (ref "SV1") (pin "5") (pinfunction "5_5") (pintype "passive"))
      (node (ref "SV1") (pin "6") (pinfunction "6_6") (pintype "passive"))
      (node (ref "SV1") (pin "7") (pinfunction "7_7") (pintype "passive"))
      (node (ref "SV1") (pin "8") (pinfunction "8_8") (pintype "passive"))
      (node (ref "U1") (pin "4") (pinfunction "GND_4") (pintype "power_in"))
      (node (ref "UCV1") (pin "P$2") (pinfunction "3_P$2") (pintype "passive"))
      (node (ref "UCV1") (pin "P$3") (pinfunction "1_P$3") (pintype "passive"))
      (node (ref "UCV2") (pin "P$2") (pinfunction "3_P$2") (pintype "passive"))
      (node (ref "UCV2") (pin "P$3") (pinfunction "1_P$3") (pintype "passive"))
      (node (ref "UCV3") (pin "P$2") (pinfunction "3_P$2") (pintype "passive"))
      (node (ref "UCV3") (pin "P$3") (pinfunction "1_P$3") (pintype "passive"))
      (node (ref "UCV4") (pin "P$2") (pinfunction "3_P$2") (pintype "passive"))
      (node (ref "UCV4") (pin "P$3") (pinfunction "1_P$3") (pintype "passive"))
      (node (ref "UCVOUT") (pin "P$3") (pinfunction "1_P$3") (pintype "passive"))
      (node (ref "UFIN1") (pin "P$2") (pinfunction "3_P$2") (pintype "passive"))
      (node (ref "UFIN1") (pin "P$3") (pinfunction "1_P$3") (pintype "passive"))
      (node (ref "UFIN2") (pin "P$2") (pinfunction "3_P$2") (pintype "passive"))
      (node (ref "UFIN2") (pin "P$3") (pinfunction "1_P$3") (pintype "passive"))
      (node (ref "UFOUT1") (pin "P$3") (pinfunction "1_P$3") (pintype "passive"))
      (node (ref "UFOUT2") (pin "P$3") (pinfunction "1_P$3") (pintype "passive"))
    )
    (net (code "62") (name "Net-(IC1A--IN)") (class "Default")
      (node (ref "IC1") (pin "2") (pinfunction "-IN_2") (pintype "input"))
      (node (ref "R101") (pin "2") (pinfunction "2_2") (pintype "passive"))
      (node (ref "R102") (pin "1") (pinfunction "1_1") (pintype "passive"))
    )
    (net (code "63") (name "Net-(IC1B--IN)") (class "Default")
      (node (ref "IC1") (pin "6") (pinfunction "-IN_6") (pintype "input"))
      (node (ref "R201") (pin "2") (pinfunction "2_2") (pintype "passive"))
      (node (ref "R202") (pin "1") (pinfunction "1_1") (pintype "passive"))
    )
    (net (code "64") (name "Net-(R103-A)") (class "Default")
      (node (ref "R103") (pin "1") (pinfunction "A_1") (pintype "passive"))
      (node (ref "R104") (pin "2") (pinfunction "2_2") (pintype "passive"))
    )
    (net (code "65") (name "Net-(R203-A)") (class "Default")
      (node (ref "R203") (pin "1") (pinfunction "A_1") (pintype "passive"))
      (node (ref "R204") (pin "2") (pinfunction "2_2") (pintype "passive"))
    )
    (net (code "66") (name "Net-(S1A-2)") (class "Default")
      (node (ref "S1") (pin "A2") (pinfunction "2_A2") (pintype "passive"))
      (node (ref "VR1") (pin "3") (pinfunction "E_3") (pintype "passive"))
    )
    (net (code "67") (name "Net-(S1B-2)") (class "Default")
      (node (ref "S1") (pin "B2") (pinfunction "2_B2") (pintype "passive"))
      (node (ref "VR1") (pin "1") (pinfunction "A_1") (pintype "passive"))
    )
    (net (code "68") (name "Net-(S2A-2)") (class "Default")
      (node (ref "S2") (pin "A2") (pinfunction "2_A2") (pintype "passive"))
      (node (ref "VR2") (pin "3") (pinfunction "E_3") (pintype "passive"))
    )
    (net (code "69") (name "Net-(S2B-2)") (class "Default")
      (node (ref "S2") (pin "B2") (pinfunction "2_B2") (pintype "passive"))
      (node (ref "VR2") (pin "1") (pinfunction "A_1") (pintype "passive"))
    )
    (net (code "70") (name "unconnected-(JP2-Pad3)") (class "Default")
      (node (ref "JP2") (pin "3") (pinfunction "3_3") (pintype "passive"))
    )
    (net (code "71") (name "unconnected-(U1-NC-Pad8)") (class "Default")
      (node (ref "U1") (pin "8") (pinfunction "NC_8") (pintype "no_connect"))
    )
    (net (code "72") (name "unconnected-(U1-NC_2-Pad1)") (class "Default")
      (node (ref "U1") (pin "1") (pinfunction "NC_2_1") (pintype "no_connect"))
    )
    (net (code "73") (name "unconnected-(U1-NC_3-Pad3)") (class "Default")
      (node (ref "U1") (pin "3") (pinfunction "NC_3_3") (pintype "no_connect"))
    )
    (net (code "74") (name "unconnected-(U1-NC_4-Pad7)") (class "Default")
      (node (ref "U1") (pin "7") (pinfunction "NC_4_7") (pintype "no_connect"))
    )
    (net (code "75") (name "unconnected-(U1-TRIM-Pad5)") (class "Default")
      (node (ref "U1") (pin "5") (pinfunction "TRIM_5") (pintype "passive"))
    )
    (net (code "76") (name "unconnected-(UCVOUT-3-PadP$2)") (class "Default")
      (node (ref "UCVOUT") (pin "P$2") (pinfunction "3_P$2") (pintype "passive"))
    )
    (net (code "77") (name "unconnected-(UFOUT1-3-PadP$2)") (class "Default")
      (node (ref "UFOUT1") (pin "P$2") (pinfunction "3_P$2") (pintype "passive"))
    )
    (net (code "78") (name "unconnected-(UFOUT2-3-PadP$2)") (class "Default")
      (node (ref "UFOUT2") (pin "P$2") (pinfunction "3_P$2") (pintype "passive"))
    )
  )
)
